# Ejection_SCH.net
KiCad netlist of a schematic drawn in Altium Designer
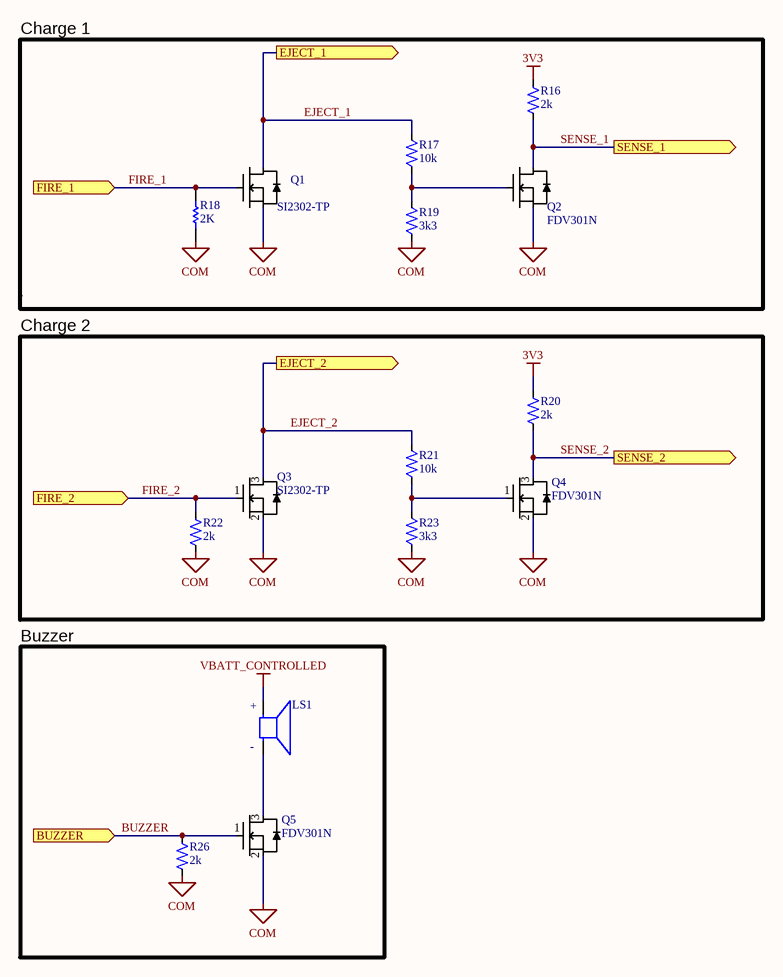
[diagram p0: Ejection_SCH.SchDoc]

(export (version "E")
  (design (tool "Eeschema 10.0.6"))
  (components
    (comp (ref "LS1")
      (value "AT-1224-TWT-12V-2-R")
      (footprint "mini-rockets:XDCR_AT-1224-TWT-12V-2-R")
      (description "AUDIO TRANSDUCER 12 VP-P 85 DB 2400 HZ")
      (fields (field (name "MF") "PUI Audio,"))
      (libsource (lib "mini-rockets") (part "AT-1224-TWT-12V-2-R"))
    )
    (comp (ref "Q1")
      (value "SI2302-TP")
      (footprint "SOT-23-3")
      (description "MOSFET N-CH 20V 3A SOT-23")
      (fields (field (name "MANUFACTURER") "Fairchild Semiconductor"))
      (libsource (lib "") (part "FDV301N_1"))
    )
    (comp (ref "Q2")
      (value "FDV301N")
      (footprint "SOT-23-3")
      (description "MOSFET N-CH 25V 220MA SOT-23")
      (fields (field (name "MANUFACTURER") "Fairchild Semiconductor"))
      (libsource (lib "") (part "FDV301N_1"))
    )
    (comp (ref "Q3")
      (value "SI2302-TP")
      (footprint "SOT-23-3")
      (description "MOSFET N-CH 20V 3A SOT-23")
      (fields (field (name "MANUFACTURER") "Fairchild Semiconductor"))
      (libsource (lib "Rockets_TRANSISTORS") (part "FDV301N"))
    )
    (comp (ref "Q4")
      (value "FDV301N")
      (footprint "SOT-23-3")
      (description "MOSFET N-CH 25V 220MA SOT-23")
      (fields (field (name "MANUFACTURER") "Fairchild Semiconductor"))
      (libsource (lib "Rockets_TRANSISTORS") (part "FDV301N"))
    )
    (comp (ref "Q5")
      (value "FDV301N")
      (footprint "SOT-23-3")
      (description "MOSFET N-CH 25V 220MA SOT-23")
      (fields (field (name "MANUFACTURER") "Fairchild Semiconductor"))
      (libsource (lib "Rockets_TRANSISTORS") (part "FDV301N"))
    )
    (comp (ref "R16")
      (value "ERJ-3GEYJ202V")
      (footprint "R0603")
      (description "RES SMD 2K OHM 5% 1/10W 0603")
      (fields (field (name "TOLERANCE") "±5%") (field (name "RESISTANCE (OHMS)") "2k"))
      (libsource (lib "Rockets_RES") (part "ERJ-3GEYJ202V"))
    )
    (comp (ref "R17")
      (value "ERJ-3GEYJ103V")
      (footprint "R0603")
      (description "RES SMD 10K OHM 5% 1/10W 0603")
      (fields (field (name "TOLERANCE") "±5%") (field (name "RESISTANCE (OHMS)") "10k"))
      (libsource (lib "Rockets_RES") (part "ERJ-3GEYJ103V"))
    )
    (comp (ref "R18")
      (value "2K")
      (footprint "RESC1608X55X30LL15T15")
      (description "RES SMD 2K OHM 5% 1/10W 0603")
      (fields (field (name "PART NUMBER") "ERJ-3GEYJ202V") (field (name "MANUFACTURER") "Panasonic"))
      (libsource (lib "Altium Content Vault") (part "RES"))
    )
    (comp (ref "R19")
      (value "ERJ-3EKF3301V")
      (footprint "R0603")
      (description "RES SMD 3.3K OHM 1% 1/10W 0603")
      (fields (field (name "TOLERANCE") "±1%") (field (name "RESISTANCE (OHMS)") "3k3"))
      (libsource (lib "Rockets_RES") (part "ERJ-3EKF3301V"))
    )
    (comp (ref "R20")
      (value "ERJ-3GEYJ202V")
      (footprint "R0603")
      (description "RES SMD 2K OHM 5% 1/10W 0603")
      (fields (field (name "TOLERANCE") "±5%") (field (name "RESISTANCE (OHMS)") "2k"))
      (libsource (lib "Rockets_RES") (part "ERJ-3GEYJ202V"))
    )
    (comp (ref "R21")
      (value "ERJ-3GEYJ103V")
      (footprint "R0603")
      (description "RES SMD 10K OHM 5% 1/10W 0603")
      (fields (field (name "TOLERANCE") "±5%") (field (name "RESISTANCE (OHMS)") "10k"))
      (libsource (lib "Rockets_RES") (part "ERJ-3GEYJ103V"))
    )
    (comp (ref "R22")
      (value "ERJ-3GEYJ202V")
      (footprint "R0603")
      (description "RES SMD 2K OHM 5% 1/10W 0603")
      (fields (field (name "TOLERANCE") "±5%") (field (name "RESISTANCE (OHMS)") "2k"))
      (libsource (lib "Rockets_RES") (part "ERJ-3GEYJ202V"))
    )
    (comp (ref "R23")
      (value "ERJ-3EKF3301V")
      (footprint "R0603")
      (description "RES SMD 3.3K OHM 1% 1/10W 0603")
      (fields (field (name "TOLERANCE") "±1%") (field (name "RESISTANCE (OHMS)") "3k3"))
      (libsource (lib "Rockets_RES") (part "ERJ-3EKF3301V"))
    )
    (comp (ref "R26")
      (value "ERJ-3GEYJ202V")
      (footprint "R0603")
      (description "RES SMD 2K OHM 5% 1/10W 0603")
      (fields (field (name "TOLERANCE") "±5%") (field (name "RESISTANCE (OHMS)") "2k"))
      (libsource (lib "Rockets_RES") (part "ERJ-3GEYJ202V"))
    )
  )
  (nets
    (net (code "1") (name "/BUZZER") (class "Default")
      (node (ref "Q5") (pin "1") (pinfunction "G_1") (pintype "passive"))
      (node (ref "R26") (pin "1") (pinfunction "1_1") (pintype "passive"))
    )
    (net (code "2") (name "/EJECT_1") (class "Default")
      (node (ref "Q1") (pin "3") (pinfunction "D_3") (pintype "passive"))
      (node (ref "R17") (pin "2") (pinfunction "2_2") (pintype "passive"))
    )
    (net (code "3") (name "/EJECT_2") (class "Default")
      (node (ref "Q3") (pin "3") (pinfunction "D_3") (pintype "passive"))
      (node (ref "R21") (pin "2") (pinfunction "2_2") (pintype "passive"))
    )
    (net (code "4") (name "/FIRE_1") (class "Default")
      (node (ref "Q1") (pin "1") (pinfunction "G_1") (pintype "passive"))
      (node (ref "R18") (pin "2") (pinfunction "2_2") (pintype "passive"))
    )
    (net (code "5") (name "/FIRE_2") (class "Default")
      (node (ref "Q3") (pin "1") (pinfunction "G_1") (pintype "passive"))
      (node (ref "R22") (pin "1") (pinfunction "1_1") (pintype "passive"))
    )
    (net (code "6") (name "/SENSE_1") (class "Default")
      (node (ref "Q2") (pin "3") (pinfunction "D_3") (pintype "passive"))
      (node (ref "R16") (pin "2") (pinfunction "2_2") (pintype "passive"))
    )
    (net (code "7") (name "/SENSE_2") (class "Default")
      (node (ref "Q4") (pin "3") (pinfunction "D_3") (pintype "passive"))
      (node (ref "R20") (pin "2") (pinfunction "2_2") (pintype "passive"))
    )
    (net (code "8") (name "3V3") (class "Default")
      (node (ref "R16") (pin "1") (pinfunction "1_1") (pintype "passive"))
      (node (ref "R20") (pin "1") (pinfunction "1_1") (pintype "passive"))
    )
    (net (code "9") (name "COM") (class "Default")
      (node (ref "Q1") (pin "2") (pinfunction "S_2") (pintype "passive"))
      (node (ref "Q2") (pin "2") (pinfunction "S_2") (pintype "passive"))
      (node (ref "Q3") (pin "2") (pinfunction "S_2") (pintype "passive"))
      (node (ref "Q4") (pin "2") (pinfunction "S_2") (pintype "passive"))
      (node (ref "Q5") (pin "2") (pinfunction "S_2") (pintype "passive"))
      (node (ref "R18") (pin "1") (pinfunction "1_1") (pintype "passive"))
      (node (ref "R19") (pin "1") (pinfunction "1_1") (pintype "passive"))
      (node (ref "R22") (pin "2") (pinfunction "2_2") (pintype "passive"))
      (node (ref "R23") (pin "1") (pinfunction "1_1") (pintype "passive"))
      (node (ref "R26") (pin "2") (pinfunction "2_2") (pintype "passive"))
    )
    (net (code "10") (name "Net-(Q2-G)") (class "Default")
      (node (ref "Q2") (pin "1") (pinfunction "G_1") (pintype "passive"))
      (node (ref "R17") (pin "1") (pinfunction "1_1") (pintype "passive"))
      (node (ref "R19") (pin "2") (pinfunction "2_2") (pintype "passive"))
    )
    (net (code "11") (name "Net-(Q4-G)") (class "Default")
      (node (ref "Q4") (pin "1") (pinfunction "G_1") (pintype "passive"))
      (node (ref "R21") (pin "1") (pinfunction "1_1") (pintype "passive"))
      (node (ref "R23") (pin "2") (pinfunction "2_2") (pintype "passive"))
    )
    (net (code "12") (name "Net-(Q5-D)") (class "Default")
      (node (ref "LS1") (pin "N") (pinfunction "N_N") (pintype "passive"))
      (node (ref "Q5") (pin "3") (pinfunction "D_3") (pintype "passive"))
    )
    (net (code "13") (name "VBATT_CONTROLLED") (class "Default")
      (node (ref "LS1") (pin "P") (pinfunction "P_P") (pintype "passive"))
    )
  )
)
